# QCopterMV_LED_KEY_Sch.net
KiCad netlist of a schematic drawn in Altium Designer
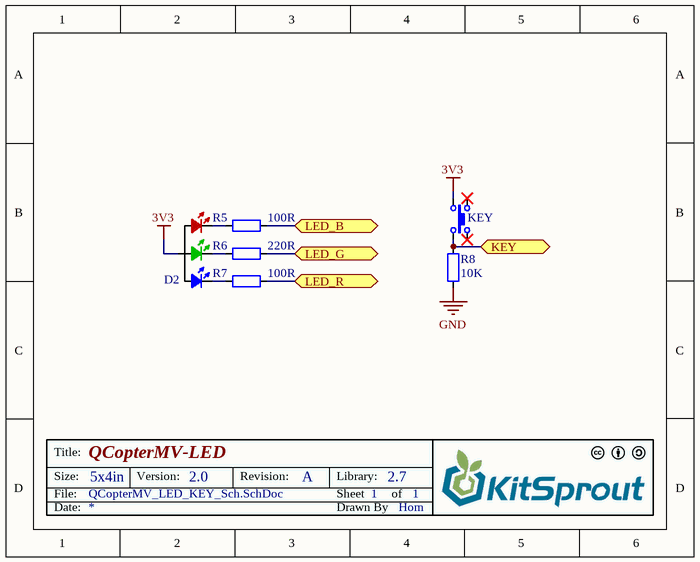
[diagram p0: QCopterMV_LED_KEY_Sch.SchDoc]

(export (version "E")
  (design (tool "Eeschema 10.0.6"))
  (components
    (comp (ref "D2")
      (value "LED_3528_RGB")
      (footprint "PCB_ActiveLED:LED_3528_RGB")
      (description "LED")
      (libsource (lib "SCH_Active") (part "LED_3528_RGB"))
    )
    (comp (ref "KEY")
      (value "ButtonTACT")
      (footprint "PCB_Switch:ButtonTACT_3.5*3.55_90")
      (description "Button")
      (libsource (lib "SCH_Switch") (part "ButtonTACT"))
    )
    (comp (ref "R5")
      (value "100R")
      (footprint "PCB_PassiveRes:RES_0603")
      (description "Resistor")
      (fields (field (name "Comment") "Res_0603"))
      (libsource (lib "SCH_Passive") (part "Res_0603"))
    )
    (comp (ref "R6")
      (value "220R")
      (footprint "PCB_PassiveRes:RES_0603")
      (description "Resistor")
      (fields (field (name "Comment") "Res_0603"))
      (libsource (lib "SCH_Passive") (part "Res_0603"))
    )
    (comp (ref "R7")
      (value "100R")
      (footprint "PCB_PassiveRes:RES_0603")
      (description "Resistor")
      (fields (field (name "Comment") "Res_0603"))
      (libsource (lib "SCH_Passive") (part "Res_0603"))
    )
    (comp (ref "R8")
      (value "10K")
      (footprint "PCB_PassiveRes:RES_0603")
      (description "Resistor")
      (fields (field (name "Comment") "Res_0603"))
      (libsource (lib "") (part "Res_0603_1"))
    )
  )
  (nets
    (net (code "1") (name "/KEY") (class "Default")
      (node (ref "KEY") (pin "4") (pinfunction "4_4") (pintype "passive"))
      (node (ref "R8") (pin "2") (pinfunction "2_2") (pintype "passive"))
    )
    (net (code "2") (name "/LED_B") (class "Default")
      (node (ref "R5") (pin "2") (pinfunction "2_2") (pintype "passive"))
    )
    (net (code "3") (name "/LED_G") (class "Default")
      (node (ref "R6") (pin "2") (pinfunction "2_2") (pintype "passive"))
    )
    (net (code "4") (name "/LED_R") (class "Default")
      (node (ref "R7") (pin "2") (pinfunction "2_2") (pintype "passive"))
    )
    (net (code "5") (name "3V3") (class "Default")
      (node (ref "D2") (pin "2") (pinfunction "A_2") (pintype "passive"))
      (node (ref "KEY") (pin "3") (pinfunction "3_3") (pintype "passive"))
    )
    (net (code "6") (name "GND") (class "Default")
      (node (ref "R8") (pin "1") (pinfunction "1_1") (pintype "passive"))
    )
    (net (code "7") (name "Net-(D2-B)") (class "Default")
      (node (ref "D2") (pin "4") (pinfunction "B_4") (pintype "passive"))
      (node (ref "R7") (pin "1") (pinfunction "1_1") (pintype "passive"))
    )
    (net (code "8") (name "Net-(D2-G)") (class "Default")
      (node (ref "D2") (pin "3") (pinfunction "G_3") (pintype "passive"))
      (node (ref "R6") (pin "1") (pinfunction "1_1") (pintype "passive"))
    )
    (net (code "9") (name "Net-(D2-R)") (class "Default")
      (node (ref "D2") (pin "1") (pinfunction "R_1") (pintype "passive"))
      (node (ref "R5") (pin "1") (pinfunction "1_1") (pintype "passive"))
    )
    (net (code "10") (name "unconnected-(KEY-Pad1)") (class "Default")
      (node (ref "KEY") (pin "1") (pinfunction "1_1") (pintype "passive+no_connect"))
    )
    (net (code "11") (name "unconnected-(KEY-Pad2)") (class "Default")
      (node (ref "KEY") (pin "2") (pinfunction "2_2") (pintype "passive+no_connect"))
    )
  )
)
